# Schematic.net
KiCad netlist of a schematic drawn in Altium Designer
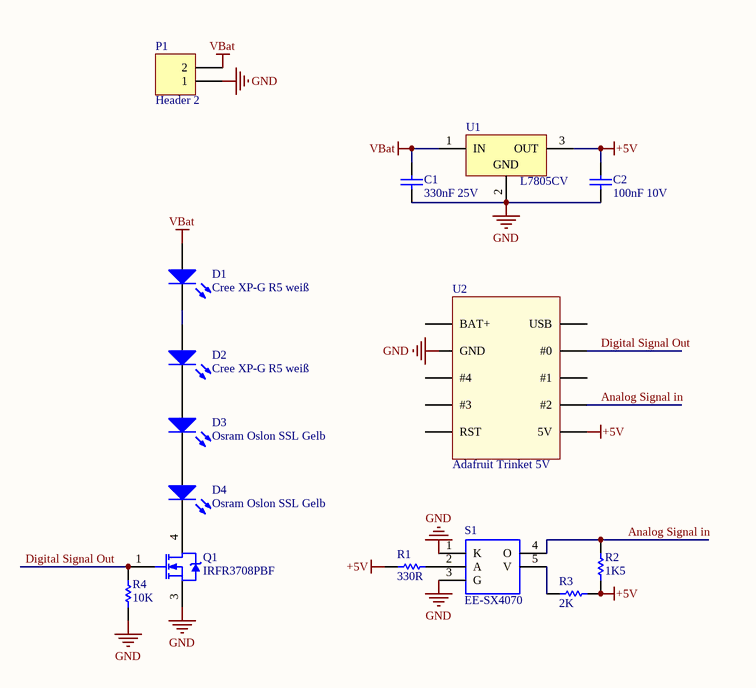
[diagram p0: Schematic.SchDoc]

(export (version "E")
  (design (tool "Eeschema 10.0.6"))
  (components
    (comp (ref "C1")
      (value "330nF 25V")
      (footprint "CAPC0603(1608)100_M")
      (description "CAP 330nF 25V -20% to +80% 0603 (1608 Metric) Thickness 1mm SMD")
      (fields (field (name "TOLERANCE") "-20% to +80%"))
      (libsource (lib "Altium Content Vault") (part "CMP-1035-02676-1"))
    )
    (comp (ref "C2")
      (value "100nF 10V")
      (footprint "CAPC0603(1608)100_L")
      (description "CAP 100nF 10V ±5% 0603 (1608 Metric) Thickness 1mm SMD")
      (fields (field (name "TOLERANCE") "Â±5%"))
      (libsource (lib "Altium Content Vault") (part "CMP-1035-02579-1"))
    )
    (comp (ref "D1")
      (value "Cree XP-G R5 weiß")
      (footprint "3.5X2.8X1.9")
      (description "Typical BLUE SiC LED")
      (fields (field (name "PUBLISHER") "Altium Limited"))
      (libsource (lib "Miscellaneous Devices") (part "LED3"))
    )
    (comp (ref "D2")
      (value "Cree XP-G R5 weiß")
      (footprint "3.5X2.8X1.9")
      (description "Typical BLUE SiC LED")
      (fields (field (name "PUBLISHER") "Altium Limited"))
      (libsource (lib "Miscellaneous Devices") (part "LED3"))
    )
    (comp (ref "D3")
      (value "Osram Oslon SSL Gelb")
      (footprint "3.5X2.8X1.9")
      (description "Typical BLUE SiC LED")
      (fields (field (name "PUBLISHER") "Altium Limited"))
      (libsource (lib "Miscellaneous Devices") (part "LED3"))
    )
    (comp (ref "D4")
      (value "Osram Oslon SSL Gelb")
      (footprint "3.5X2.8X1.9")
      (description "Typical BLUE SiC LED")
      (fields (field (name "PUBLISHER") "Altium Limited"))
      (libsource (lib "Miscellaneous Devices") (part "LED3"))
    )
    (comp (ref "P1")
      (value "Header 2")
      (footprint "HDR1X2")
      (description "Header, 2-Pin")
      (fields (field (name "PUBLISHER") "Altium Limited"))
      (libsource (lib "Miscellaneous Connectors") (part "Header 2"))
    )
    (comp (ref "Q1")
      (value "IRFR3708PBF")
      (footprint "INTR-TO-252AA-3_M")
      (description "Mosfet N-Channel, 30 V, 61 A, -55 to 175 degC, 3-Pin DPAK, RoHS, Tube")
      (fields (field (name "MANUFACTURER") "International Rectifier"))
      (libsource (lib "Altium Content Vault") (part "CMP-2000-05156-1"))
    )
    (comp (ref "R1")
      (value "330R")
      (footprint "RESC0603(1608)_L")
      (description "330R 0.1W 5% 0603 (1608 Metric)  SMD")
      (fields (field (name "TOLERANCE") "5 %") (field (name "POWER") "0.1 W"))
      (libsource (lib "Altium Content Vault") (part "CMP-1012-00062-1"))
    )
    (comp (ref "R2")
      (value "1K5")
      (footprint "RESC0603(1608)_L")
      (description "1K5 0.1W 1% 0603 (1608 Metric)  SMD")
      (fields (field (name "POWER") "0.1 W") (field (name "TOLERANCE") "1 %"))
      (libsource (lib "Altium Content Vault") (part "CMP-1012-00528-1"))
    )
    (comp (ref "R3")
      (value "2K")
      (footprint "RESC0603(1608)_N")
      (description "2K 0.1W 1% 0603 (1608 Metric)  SMD")
      (fields (field (name "POWER") "0.1 W") (field (name "TOLERANCE") "1 %"))
      (libsource (lib "Altium Content Vault") (part "CMP-1012-00542-1"))
    )
    (comp (ref "R4")
      (value "10K")
      (footprint "RESC0603(1608)_N")
      (description "10K 0.1W 1% 0603 (1608 Metric)  SMD")
      (fields (field (name "POWER") "0.1 W") (field (name "TOLERANCE") "1 %"))
      (libsource (lib "Altium Content Vault") (part "CMP-1012-00623-1"))
    )
    (comp (ref "S1")
      (value "EE-SX4070")
      (footprint "EE-SX4070")
      (description "Slotted photo switch,EE-SX4070 8mm W Omron EE-SX4070 Through Hole Slotted Optical Switch")
      (fields (field (name "RS PART NUMBER") "2192527"))
      (libsource (lib "EE-SX4070") (part "EE-SX4070"))
    )
    (comp (ref "U1")
      (value "L7805CV")
      (footprint "TO220")
      (description "Positive Voltage Regulator, 5V, 3-Pin TO-220")
      (libsource (lib "Altium Content Vault") (part "CMP-0244-00483-1"))
    )
    (comp (ref "U2")
      (value "Adafruit Trinket 5V")
      (libsource (lib "Eigene_Lib") (part "Adafruit Trinket 5V"))
    )
  )
  (nets
    (net (code "1") (name "+5V") (class "Default")
      (node (ref "C2") (pin "2") (pinfunction "2_2") (pintype "passive"))
      (node (ref "R1") (pin "1") (pinfunction "1_1") (pintype "passive"))
      (node (ref "R2") (pin "1") (pinfunction "1_1") (pintype "passive"))
      (node (ref "R3") (pin "2") (pinfunction "2_2") (pintype "passive"))
      (node (ref "U1") (pin "3") (pinfunction "OUT_3") (pintype "power_in"))
      (node (ref "U2") (pin "10") (pinfunction "5V_10") (pintype "passive"))
    )
    (net (code "2") (name "/Analog Signal in") (class "Default")
      (node (ref "R2") (pin "2") (pinfunction "2_2") (pintype "passive"))
      (node (ref "S1") (pin "4") (pinfunction "O_4") (pintype "passive"))
      (node (ref "U2") (pin "9") (pinfunction "#2_9") (pintype "passive"))
    )
    (net (code "3") (name "/Digital Signal Out") (class "Default")
      (node (ref "Q1") (pin "1") (pinfunction "G_1") (pintype "passive"))
      (node (ref "R4") (pin "2") (pinfunction "2_2") (pintype "passive"))
      (node (ref "U2") (pin "7") (pinfunction "#0_7") (pintype "passive"))
    )
    (net (code "4") (name "GND") (class "Default")
      (node (ref "C1") (pin "1") (pinfunction "1_1") (pintype "passive"))
      (node (ref "C2") (pin "1") (pinfunction "1_1") (pintype "passive"))
      (node (ref "P1") (pin "1") (pinfunction "1_1") (pintype "passive"))
      (node (ref "Q1") (pin "3") (pinfunction "S_3") (pintype "passive"))
      (node (ref "R4") (pin "1") (pinfunction "1_1") (pintype "passive"))
      (node (ref "S1") (pin "1") (pinfunction "K_1") (pintype "passive"))
      (node (ref "S1") (pin "3") (pinfunction "G_3") (pintype "passive"))
      (node (ref "U1") (pin "2") (pinfunction "GND_2") (pintype "power_in"))
    )
    (net (code "5") (name "Net-(D1-K)") (class "Default")
      (node (ref "D1") (pin "2") (pinfunction "K_2") (pintype "passive"))
      (node (ref "D2") (pin "1") (pinfunction "A_1") (pintype "passive"))
    )
    (net (code "6") (name "Net-(D2-K)") (class "Default")
      (node (ref "D2") (pin "2") (pinfunction "K_2") (pintype "passive"))
      (node (ref "D3") (pin "1") (pinfunction "A_1") (pintype "passive"))
    )
    (net (code "7") (name "Net-(D3-K)") (class "Default")
      (node (ref "D3") (pin "2") (pinfunction "K_2") (pintype "passive"))
      (node (ref "D4") (pin "1") (pinfunction "A_1") (pintype "passive"))
    )
    (net (code "8") (name "Net-(D4-K)") (class "Default")
      (node (ref "D4") (pin "2") (pinfunction "K_2") (pintype "passive"))
      (node (ref "Q1") (pin "4") (pinfunction "D_4") (pintype "passive"))
    )
    (net (code "9") (name "Net-(S1-A)") (class "Default")
      (node (ref "R1") (pin "2") (pinfunction "2_2") (pintype "passive"))
      (node (ref "S1") (pin "2") (pinfunction "A_2") (pintype "passive"))
    )
    (net (code "10") (name "Net-(S1-V)") (class "Default")
      (node (ref "R3") (pin "1") (pinfunction "1_1") (pintype "passive"))
      (node (ref "S1") (pin "5") (pinfunction "V_5") (pintype "passive"))
    )
    (net (code "11") (name "VBat") (class "Default")
      (node (ref "C1") (pin "2") (pinfunction "2_2") (pintype "passive"))
      (node (ref "D1") (pin "1") (pinfunction "A_1") (pintype "passive"))
      (node (ref "P1") (pin "2") (pinfunction "2_2") (pintype "passive"))
      (node (ref "U1") (pin "1") (pinfunction "IN_1") (pintype "power_in"))
    )
    (net (code "12") (name "unconnected-(U2-#1-Pad8)") (class "Default")
      (node (ref "U2") (pin "8") (pinfunction "#1_8") (pintype "passive"))
    )
    (net (code "13") (name "unconnected-(U2-#3-Pad4)") (class "Default")
      (node (ref "U2") (pin "4") (pinfunction "#3_4") (pintype "passive"))
    )
    (net (code "14") (name "unconnected-(U2-#4-Pad3)") (class "Default")
      (node (ref "U2") (pin "3") (pinfunction "#4_3") (pintype "passive"))
    )
    (net (code "15") (name "unconnected-(U2-BAT+-Pad1)") (class "Default")
      (node (ref "U2") (pin "1") (pinfunction "BAT+_1") (pintype "passive"))
    )
    (net (code "16") (name "unconnected-(U2-GND-Pad2)") (class "Default")
      (node (ref "U2") (pin "2") (pinfunction "GND_2") (pintype "passive"))
    )
    (net (code "17") (name "unconnected-(U2-RST-Pad5)") (class "Default")
      (node (ref "U2") (pin "5") (pinfunction "RST_5") (pintype "passive"))
    )
    (net (code "18") (name "unconnected-(U2-USB-Pad6)") (class "Default")
      (node (ref "U2") (pin "6") (pinfunction "USB_6") (pintype "passive"))
    )
  )
)
